# 60.net
KiCad netlist of a schematic drawn in Altium Designer
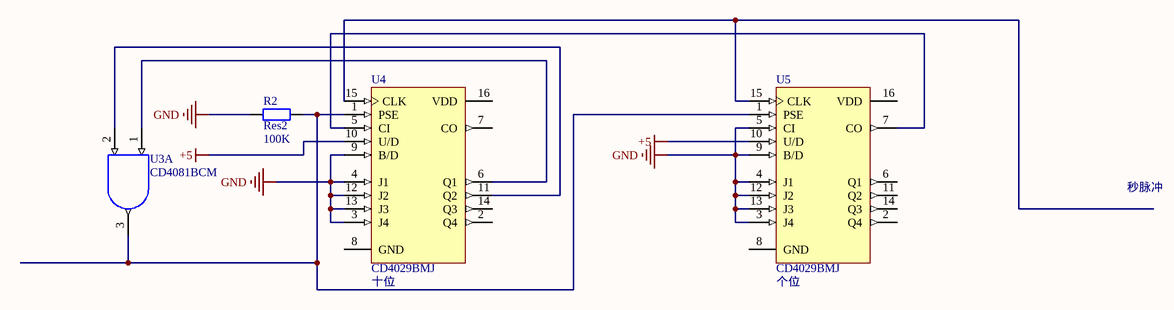
[diagram p0: 60进制计数器.SchDoc]

(export (version "E")
  (design (tool "Eeschema 10.0.6"))
  (components
    (comp (ref "R2")
      (value "Res2")
      (footprint "AXIAL-0.4")
      (description "Resistor")
      (fields (field (name "ALTIUM_VALUE") "100K") (field (name "PUBLISHER") "Altium Limited"))
      (libsource (lib "Miscellaneous Devices") (part "Res2"))
    )
    (comp (ref "U3")
      (value "CD4081BCM")
      (footprint "M14A_N")
      (description "Quad 2-Input AND Buffered B series Gate, 14-Pin SOIC")
      (fields (field (name "PUBLISHER") "Altium Limited"))
      (libsource (lib "FSC Logic Gate") (part "CD4081BCM"))
    )
    (comp (ref "U4")
      (value "CD4029BMJ")
      (footprint "J16A")
      (description "Binary/Decade Up/Down Counter")
      (fields (field (name "PUBLISHER") "Altium Limited"))
      (libsource (lib "NSC Logic Counter") (part "CD4029BMJ"))
    )
    (comp (ref "U5")
      (value "CD4029BMJ")
      (footprint "J16A")
      (description "Binary/Decade Up/Down Counter")
      (fields (field (name "PUBLISHER") "Altium Limited"))
      (libsource (lib "NSC Logic Counter") (part "CD4029BMJ"))
    )
  )
  (nets
    (net (code "1") (name "+5") (class "Default")
      (node (ref "U4") (pin "10") (pinfunction "U/D_10") (pintype "input"))
      (node (ref "U5") (pin "10") (pinfunction "U/D_10") (pintype "input"))
    )
    (net (code "2") (name "GND") (class "Default")
      (node (ref "R2") (pin "1") (pinfunction "1_1") (pintype "passive"))
      (node (ref "U3") (pin "7") (pinfunction "GND_7") (pintype "power_in"))
      (node (ref "U4") (pin "12") (pinfunction "J2_12") (pintype "input"))
      (node (ref "U4") (pin "13") (pinfunction "J3_13") (pintype "input"))
      (node (ref "U4") (pin "3") (pinfunction "J4_3") (pintype "input"))
      (node (ref "U4") (pin "4") (pinfunction "J1_4") (pintype "input"))
      (node (ref "U4") (pin "9") (pinfunction "B/D_9") (pintype "input"))
      (node (ref "U5") (pin "12") (pinfunction "J2_12") (pintype "input"))
      (node (ref "U5") (pin "13") (pinfunction "J3_13") (pintype "input"))
      (node (ref "U5") (pin "3") (pinfunction "J4_3") (pintype "input"))
      (node (ref "U5") (pin "4") (pinfunction "J1_4") (pintype "input"))
      (node (ref "U5") (pin "5") (pinfunction "CI_5") (pintype "input"))
      (node (ref "U5") (pin "9") (pinfunction "B/D_9") (pintype "input"))
    )
    (net (code "3") (name "Net-(U3A-A)") (class "Default")
      (node (ref "U3") (pin "1") (pinfunction "A_1") (pintype "input"))
      (node (ref "U4") (pin "6") (pinfunction "Q1_6") (pintype "output"))
    )
    (net (code "4") (name "Net-(U3A-B)") (class "Default")
      (node (ref "U3") (pin "2") (pinfunction "B_2") (pintype "input"))
      (node (ref "U4") (pin "11") (pinfunction "Q2_11") (pintype "output"))
    )
    (net (code "5") (name "Net-(U3A-J)") (class "Default")
      (node (ref "R2") (pin "2") (pinfunction "2_2") (pintype "passive"))
      (node (ref "U3") (pin "3") (pinfunction "J_3") (pintype "output"))
      (node (ref "U4") (pin "1") (pinfunction "PSE_1") (pintype "input"))
      (node (ref "U5") (pin "1") (pinfunction "PSE_1") (pintype "input"))
    )
    (net (code "6") (name "Net-(U4-CI)") (class "Default")
      (node (ref "U4") (pin "5") (pinfunction "CI_5") (pintype "input"))
      (node (ref "U5") (pin "7") (pinfunction "CO_7") (pintype "output"))
    )
    (net (code "7") (name "Net-(U4-CLK)") (class "Default")
      (node (ref "U4") (pin "15") (pinfunction "CLK_15") (pintype "input"))
      (node (ref "U5") (pin "15") (pinfunction "CLK_15") (pintype "input"))
    )
    (net (code "8") (name "VDD") (class "Default")
      (node (ref "U3") (pin "14") (pinfunction "VDD_14") (pintype "power_in"))
    )
    (net (code "9") (name "unconnected-(U4-CO-Pad7)") (class "Default")
      (node (ref "U4") (pin "7") (pinfunction "CO_7") (pintype "output"))
    )
    (net (code "10") (name "unconnected-(U4-GND-Pad8)") (class "Default")
      (node (ref "U4") (pin "8") (pinfunction "GND_8") (pintype "power_in"))
    )
    (net (code "11") (name "unconnected-(U4-Q3-Pad14)") (class "Default")
      (node (ref "U4") (pin "14") (pinfunction "Q3_14") (pintype "output"))
    )
    (net (code "12") (name "unconnected-(U4-Q4-Pad2)") (class "Default")
      (node (ref "U4") (pin "2") (pinfunction "Q4_2") (pintype "output"))
    )
    (net (code "13") (name "unconnected-(U4-VDD-Pad16)") (class "Default")
      (node (ref "U4") (pin "16") (pinfunction "VDD_16") (pintype "power_in"))
    )
    (net (code "14") (name "unconnected-(U5-GND-Pad8)") (class "Default")
      (node (ref "U5") (pin "8") (pinfunction "GND_8") (pintype "power_in"))
    )
    (net (code "15") (name "unconnected-(U5-Q1-Pad6)") (class "Default")
      (node (ref "U5") (pin "6") (pinfunction "Q1_6") (pintype "output"))
    )
    (net (code "16") (name "unconnected-(U5-Q2-Pad11)") (class "Default")
      (node (ref "U5") (pin "11") (pinfunction "Q2_11") (pintype "output"))
    )
    (net (code "17") (name "unconnected-(U5-Q3-Pad14)") (class "Default")
      (node (ref "U5") (pin "14") (pinfunction "Q3_14") (pintype "output"))
    )
    (net (code "18") (name "unconnected-(U5-Q4-Pad2)") (class "Default")
      (node (ref "U5") (pin "2") (pinfunction "Q4_2") (pintype "output"))
    )
    (net (code "19") (name "unconnected-(U5-VDD-Pad16)") (class "Default")
      (node (ref "U5") (pin "16") (pinfunction "VDD_16") (pintype "power_in"))
    )
  )
)
